# motors-state-monitor.net
KiCad netlist of a schematic drawn in Altium Designer
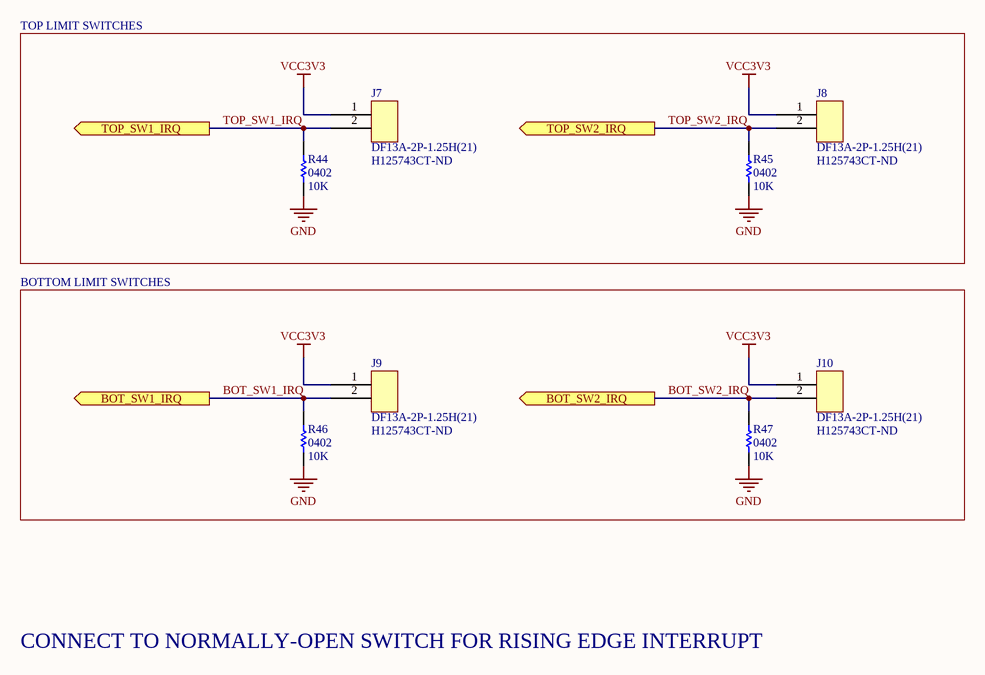
[diagram p0: motors-state-monitor.SchDoc]

(export (version "E")
  (design (tool "Eeschema 10.0.6"))
  (components
    (comp (ref "J7")
      (value "DF13A-2P-1.25H(21)")
      (footprint "DF13A-2P-1.25H(21)")
      (description "2 pos DF13 right angle surface mount connector")
      (fields (field (name "SUPPLIER PART NUMBER 1") "H125743CT-ND"))
      (libsource (lib "DF13A-2P-1.25H(21)") (part "DF13A-2P-1.25H(21)"))
    )
    (comp (ref "J8")
      (value "DF13A-2P-1.25H(21)")
      (footprint "DF13A-2P-1.25H(21)")
      (description "2 pos DF13 right angle surface mount connector")
      (fields (field (name "SUPPLIER PART NUMBER 1") "H125743CT-ND"))
      (libsource (lib "DF13A-2P-1.25H(21)") (part "DF13A-2P-1.25H(21)"))
    )
    (comp (ref "J9")
      (value "DF13A-2P-1.25H(21)")
      (footprint "DF13A-2P-1.25H(21)")
      (description "2 pos DF13 right angle surface mount connector")
      (fields (field (name "SUPPLIER PART NUMBER 1") "H125743CT-ND"))
      (libsource (lib "DF13A-2P-1.25H(21)") (part "DF13A-2P-1.25H(21)"))
    )
    (comp (ref "J10")
      (value "DF13A-2P-1.25H(21)")
      (footprint "DF13A-2P-1.25H(21)")
      (description "2 pos DF13 right angle surface mount connector")
      (fields (field (name "SUPPLIER PART NUMBER 1") "H125743CT-ND"))
      (libsource (lib "DF13A-2P-1.25H(21)") (part "DF13A-2P-1.25H(21)"))
    )
    (comp (ref "R44")
      (value "0402")
      (footprint "RES0402R")
      (description "0402 resistor")
      (fields
        (field (name "ALTIUM_VALUE") "10K")
        (field (name "MANUFACTURER") "Panasonic")
        (field (name "MANUFACTURER PART NUMBER") "ERJ-2RKF1002X")
      )
      (libsource (lib "heron-general") (part "RES0402"))
    )
    (comp (ref "R45")
      (value "0402")
      (footprint "RES0402R")
      (description "0402 resistor")
      (fields
        (field (name "ALTIUM_VALUE") "10K")
        (field (name "MANUFACTURER") "Panasonic")
        (field (name "MANUFACTURER PART NUMBER") "ERJ-2RKF1002X")
      )
      (libsource (lib "heron-general") (part "RES0402"))
    )
    (comp (ref "R46")
      (value "0402")
      (footprint "RES0402R")
      (description "0402 resistor")
      (fields
        (field (name "ALTIUM_VALUE") "10K")
        (field (name "MANUFACTURER") "Panasonic")
        (field (name "MANUFACTURER PART NUMBER") "ERJ-2RKF1002X")
      )
      (libsource (lib "heron-general") (part "RES0402"))
    )
    (comp (ref "R47")
      (value "0402")
      (footprint "RES0402R")
      (description "0402 resistor")
      (fields
        (field (name "ALTIUM_VALUE") "10K")
        (field (name "MANUFACTURER") "Panasonic")
        (field (name "MANUFACTURER PART NUMBER") "ERJ-2RKF1002X")
      )
      (libsource (lib "heron-general") (part "RES0402"))
    )
  )
  (nets
    (net (code "1") (name "/BOT_SW1_IRQ") (class "Default")
      (node (ref "J9") (pin "2") (pintype "passive"))
      (node (ref "R46") (pin "2") (pinfunction "2_2") (pintype "passive"))
    )
    (net (code "2") (name "/BOT_SW2_IRQ") (class "Default")
      (node (ref "J10") (pin "2") (pintype "passive"))
      (node (ref "R47") (pin "2") (pinfunction "2_2") (pintype "passive"))
    )
    (net (code "3") (name "/TOP_SW1_IRQ") (class "Default")
      (node (ref "J7") (pin "2") (pintype "passive"))
      (node (ref "R44") (pin "2") (pinfunction "2_2") (pintype "passive"))
    )
    (net (code "4") (name "/TOP_SW2_IRQ") (class "Default")
      (node (ref "J8") (pin "2") (pintype "passive"))
      (node (ref "R45") (pin "2") (pinfunction "2_2") (pintype "passive"))
    )
    (net (code "5") (name "GND") (class "Default")
      (node (ref "R44") (pin "1") (pinfunction "1_1") (pintype "passive"))
      (node (ref "R45") (pin "1") (pinfunction "1_1") (pintype "passive"))
      (node (ref "R46") (pin "1") (pinfunction "1_1") (pintype "passive"))
      (node (ref "R47") (pin "1") (pinfunction "1_1") (pintype "passive"))
    )
    (net (code "6") (name "VCC3V3") (class "Default")
      (node (ref "J10") (pin "1") (pintype "passive"))
      (node (ref "J7") (pin "1") (pintype "passive"))
      (node (ref "J8") (pin "1") (pintype "passive"))
      (node (ref "J9") (pin "1") (pintype "passive"))
    )
  )
)
